# MySensorMicro.net
KiCad netlist of a schematic drawn in EAGLE
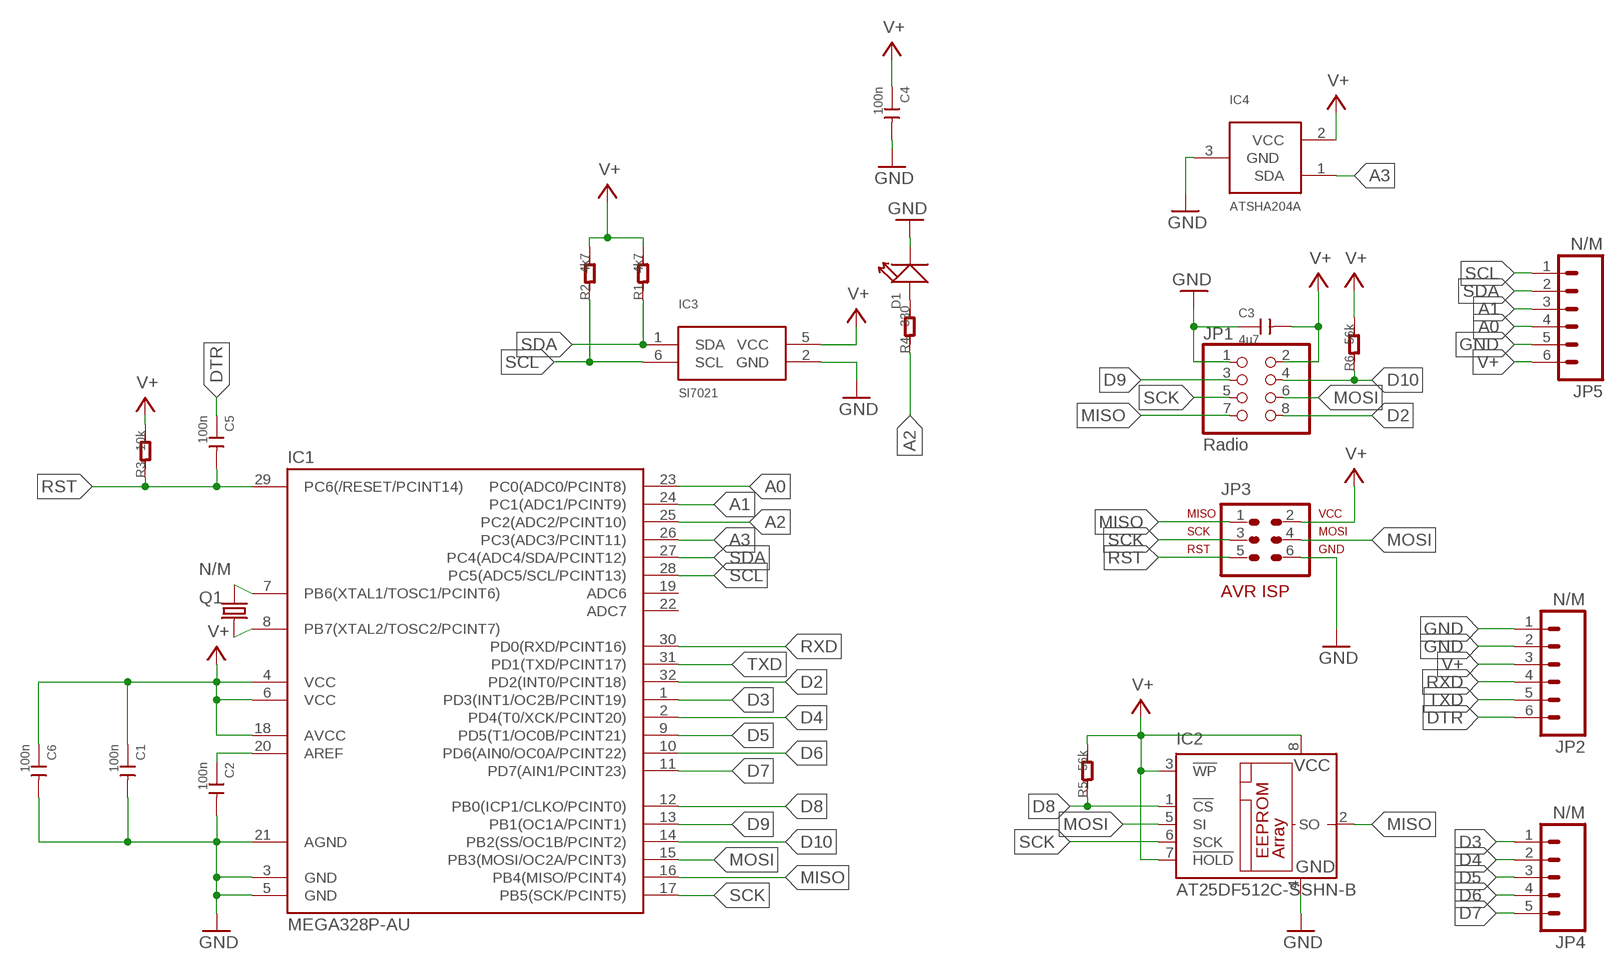
[diagram p0: schematic, sheet 1]

(export (version "E")
  (design (tool "Eeschema 10.0.6"))
  (components
    (comp (ref "C1")
      (value "100n")
      (footprint "eagle-import:C0402")
      (libsource (lib "eagle-import") (part "CAP-0402"))
    )
    (comp (ref "C2")
      (value "100n")
      (footprint "eagle-import:C0402")
      (libsource (lib "eagle-import") (part "CAP-0402"))
    )
    (comp (ref "C3")
      (value "4u7")
      (footprint "eagle-import:C0603")
      (libsource (lib "eagle-import") (part "CAP-0603"))
    )
    (comp (ref "C4")
      (value "100n")
      (footprint "eagle-import:C0402")
      (libsource (lib "eagle-import") (part "CAP-0402"))
    )
    (comp (ref "C5")
      (value "100n")
      (footprint "eagle-import:C0402")
      (libsource (lib "eagle-import") (part "CAP-0402"))
    )
    (comp (ref "C6")
      (value "100n")
      (footprint "eagle-import:C0402")
      (libsource (lib "eagle-import") (part "CAP-0402"))
    )
    (comp (ref "D1")
      (value "LED-0402")
      (footprint "eagle-import:LED-0402")
      (libsource (lib "eagle-import") (part "LED-0402"))
    )
    (comp (ref "IC1")
      (value "MEGA328P-AU")
      (footprint "eagle-import:TQFP32-08")
      (libsource (lib "eagle-import") (part "MEGA48/88/168-AU"))
    )
    (comp (ref "IC2")
      (value "AT25DF512C-SSHN-B")
      (footprint "eagle-import:SO-08")
      (fields (field (name "MF") "MICROCHIP") (field (name "MPN") "25AA080/SN"))
      (libsource (lib "eagle-import") (part "25SNAA080"))
    )
    (comp (ref "IC3")
      (value "SI7021")
      (footprint "eagle-import:DFN6")
      (libsource (lib "eagle-import") (part "SI7021"))
    )
    (comp (ref "IC4")
      (value "ATSHA204A")
      (footprint "eagle-import:SOT23")
      (libsource (lib "eagle-import") (part "ATSHA204A"))
    )
    (comp (ref "JP1")
      (value "Radio")
      (footprint "eagle-import:2X04")
      (libsource (lib "eagle-import") (part "PINHD-2X4"))
    )
    (comp (ref "JP2")
      (value "N/M")
      (footprint "eagle-import:1X06_NO_SILK")
      (libsource (lib "eagle-import") (part "M06NO_SILK_FEMALE_PTH"))
    )
    (comp (ref "JP3")
      (value "N/M")
      (footprint "eagle-import:AVR-ISP-6")
      (libsource (lib "eagle-import") (part "AVR-ISP-6VERT"))
    )
    (comp (ref "JP4")
      (value "N/M")
      (footprint "eagle-import:1X05_NO_SILK")
      (libsource (lib "eagle-import") (part "M05NO_SILK"))
    )
    (comp (ref "JP5")
      (value "N/M")
      (footprint "eagle-import:1X06_NO_SILK")
      (libsource (lib "eagle-import") (part "M06NO_SILK_FEMALE_PTH"))
    )
    (comp (ref "Q1")
      (value "N/M")
      (footprint "eagle-import:2P-L3.2XW1.5MM")
      (libsource (lib "eagle-import") (part "CRYSTAL-306010055"))
    )
    (comp (ref "R1")
      (value "4k7")
      (footprint "eagle-import:R0402")
      (libsource (lib "eagle-import") (part "R-0402"))
    )
    (comp (ref "R2")
      (value "4k7")
      (footprint "eagle-import:R0402")
      (libsource (lib "eagle-import") (part "R-0402"))
    )
    (comp (ref "R3")
      (value "10k")
      (footprint "eagle-import:R0402")
      (libsource (lib "eagle-import") (part "R-0402"))
    )
    (comp (ref "R4")
      (value "330")
      (footprint "eagle-import:R0402")
      (libsource (lib "eagle-import") (part "R-0402"))
    )
    (comp (ref "R5")
      (value "56k")
      (footprint "eagle-import:R0402")
      (libsource (lib "eagle-import") (part "R-0402"))
    )
    (comp (ref "R6")
      (value "56k")
      (footprint "eagle-import:R0402")
      (libsource (lib "eagle-import") (part "R-0402"))
    )
  )
  (nets
    (net (code "1") (name "A0") (class "Default")
      (node (ref "IC1") (pin "23") (pinfunction "PC0(ADC0/PCINT8)_23") (pintype "bidirectional"))
      (node (ref "JP5") (pin "4") (pinfunction "4_4") (pintype "passive"))
    )
    (net (code "2") (name "A1") (class "Default")
      (node (ref "IC1") (pin "24") (pinfunction "PC1(ADC1/PCINT9)_24") (pintype "bidirectional"))
      (node (ref "JP5") (pin "3") (pinfunction "3_3") (pintype "passive"))
    )
    (net (code "3") (name "A2") (class "Default")
      (node (ref "IC1") (pin "25") (pinfunction "PC2(ADC2/PCINT10)_25") (pintype "bidirectional"))
      (node (ref "R4") (pin "1") (pinfunction "1_1") (pintype "bidirectional"))
    )
    (net (code "4") (name "A3") (class "Default")
      (node (ref "IC1") (pin "26") (pinfunction "PC3(ADC3/PCINT11)_26") (pintype "bidirectional"))
      (node (ref "IC4") (pin "1") (pinfunction "SDA_1") (pintype "bidirectional"))
    )
    (net (code "5") (name "D2") (class "Default")
      (node (ref "IC1") (pin "32") (pinfunction "PD2(INT0/PCINT18)_32") (pintype "bidirectional"))
      (node (ref "JP1") (pin "8") (pinfunction "8_8") (pintype "passive"))
    )
    (net (code "6") (name "D3") (class "Default")
      (node (ref "IC1") (pin "1") (pinfunction "PD3(INT1/OC2B/PCINT19)_1") (pintype "bidirectional"))
      (node (ref "JP4") (pin "1") (pinfunction "1_1") (pintype "passive"))
    )
    (net (code "7") (name "D4") (class "Default")
      (node (ref "IC1") (pin "2") (pinfunction "PD4(T0/XCK/PCINT20)_2") (pintype "bidirectional"))
      (node (ref "JP4") (pin "2") (pinfunction "2_2") (pintype "passive"))
    )
    (net (code "8") (name "D5") (class "Default")
      (node (ref "IC1") (pin "9") (pinfunction "PD5(T1/OC0B/PCINT21)_9") (pintype "bidirectional"))
      (node (ref "JP4") (pin "3") (pinfunction "3_3") (pintype "passive"))
    )
    (net (code "9") (name "D6") (class "Default")
      (node (ref "IC1") (pin "10") (pinfunction "PD6(AIN0/OC0A/PCINT22)_10") (pintype "bidirectional"))
      (node (ref "JP4") (pin "4") (pinfunction "4_4") (pintype "passive"))
    )
    (net (code "10") (name "D7") (class "Default")
      (node (ref "IC1") (pin "11") (pinfunction "PD7(AIN1/PCINT23)_11") (pintype "bidirectional"))
      (node (ref "JP4") (pin "5") (pinfunction "5_5") (pintype "passive"))
    )
    (net (code "11") (name "D8") (class "Default")
      (node (ref "IC1") (pin "12") (pinfunction "PB0(ICP1/CLKO/PCINT0)_12") (pintype "bidirectional"))
      (node (ref "IC2") (pin "1") (pinfunction "~{CS}_1") (pintype "input"))
      (node (ref "R5") (pin "1") (pinfunction "1_1") (pintype "bidirectional"))
    )
    (net (code "12") (name "D9") (class "Default")
      (node (ref "IC1") (pin "13") (pinfunction "PB1(OC1A/PCINT1)_13") (pintype "bidirectional"))
      (node (ref "JP1") (pin "3") (pinfunction "3_3") (pintype "passive"))
    )
    (net (code "13") (name "D10") (class "Default")
      (node (ref "IC1") (pin "14") (pinfunction "PB2(SS/OC1B/PCINT2)_14") (pintype "bidirectional"))
      (node (ref "JP1") (pin "4") (pinfunction "4_4") (pintype "passive"))
      (node (ref "R6") (pin "1") (pinfunction "1_1") (pintype "bidirectional"))
    )
    (net (code "14") (name "DTR") (class "Default")
      (node (ref "C5") (pin "1") (pinfunction "1_1") (pintype "passive"))
      (node (ref "JP2") (pin "6") (pinfunction "6_6") (pintype "passive"))
    )
    (net (code "15") (name "GND") (class "Default")
      (node (ref "C1") (pin "2") (pinfunction "2_2") (pintype "passive"))
      (node (ref "C2") (pin "2") (pinfunction "2_2") (pintype "passive"))
      (node (ref "C3") (pin "1") (pinfunction "1_1") (pintype "passive"))
      (node (ref "C4") (pin "2") (pinfunction "2_2") (pintype "passive"))
      (node (ref "C6") (pin "2") (pinfunction "2_2") (pintype "passive"))
      (node (ref "D1") (pin "-") (pinfunction "-_-") (pintype "passive"))
      (node (ref "IC1") (pin "21") (pinfunction "AGND_21") (pintype "power_in"))
      (node (ref "IC1") (pin "3") (pinfunction "GND_3") (pintype "power_in"))
      (node (ref "IC1") (pin "5") (pinfunction "GND_5") (pintype "power_in"))
      (node (ref "IC2") (pin "4") (pinfunction "GND_4") (pintype "power_in"))
      (node (ref "IC3") (pin "2") (pinfunction "GND_2") (pintype "bidirectional"))
      (node (ref "IC4") (pin "3") (pinfunction "GND_3") (pintype "bidirectional"))
      (node (ref "JP1") (pin "1") (pinfunction "1_1") (pintype "passive"))
      (node (ref "JP2") (pin "1") (pinfunction "1_1") (pintype "passive"))
      (node (ref "JP2") (pin "2") (pinfunction "2_2") (pintype "passive"))
      (node (ref "JP3") (pin "6") (pinfunction "6_6") (pintype "passive"))
      (node (ref "JP5") (pin "5") (pinfunction "5_5") (pintype "passive"))
    )
    (net (code "16") (name "MISO") (class "Default")
      (node (ref "IC1") (pin "16") (pinfunction "PB4(MISO/PCINT4)_16") (pintype "bidirectional"))
      (node (ref "IC2") (pin "2") (pinfunction "SO_2") (pintype "bidirectional"))
      (node (ref "JP1") (pin "7") (pinfunction "7_7") (pintype "passive"))
      (node (ref "JP3") (pin "1") (pinfunction "1_1") (pintype "passive"))
    )
    (net (code "17") (name "MOSI") (class "Default")
      (node (ref "IC1") (pin "15") (pinfunction "PB3(MOSI/OC2A/PCINT3)_15") (pintype "bidirectional"))
      (node (ref "IC2") (pin "5") (pinfunction "SI_5") (pintype "input"))
      (node (ref "JP1") (pin "6") (pinfunction "6_6") (pintype "passive"))
      (node (ref "JP3") (pin "4") (pinfunction "4_4") (pintype "passive"))
    )
    (net (code "18") (name "Net-(D1-Pad+)") (class "Default")
      (node (ref "D1") (pin "+") (pinfunction "+_+") (pintype "passive"))
      (node (ref "R4") (pin "2") (pinfunction "2_2") (pintype "bidirectional"))
    )
    (net (code "19") (name "Net-(IC1-AREF)") (class "Default")
      (node (ref "C2") (pin "1") (pinfunction "1_1") (pintype "passive"))
      (node (ref "IC1") (pin "20") (pinfunction "AREF_20") (pintype "passive"))
    )
    (net (code "20") (name "Net-(IC1-PB6(XTAL1{slash}TOSC1{slash}PCINT6))") (class "Default")
      (node (ref "IC1") (pin "7") (pinfunction "PB6(XTAL1/TOSC1/PCINT6)_7") (pintype "bidirectional"))
      (node (ref "Q1") (pin "1") (pinfunction "1_1") (pintype "passive"))
    )
    (net (code "21") (name "Net-(IC1-PB7(XTAL2{slash}TOSC2{slash}PCINT7))") (class "Default")
      (node (ref "IC1") (pin "8") (pinfunction "PB7(XTAL2/TOSC2/PCINT7)_8") (pintype "bidirectional"))
      (node (ref "Q1") (pin "2") (pinfunction "2_2") (pintype "passive"))
    )
    (net (code "22") (name "RST") (class "Default")
      (node (ref "C5") (pin "2") (pinfunction "2_2") (pintype "passive"))
      (node (ref "IC1") (pin "29") (pinfunction "PC6(/RESET/PCINT14)_29") (pintype "bidirectional"))
      (node (ref "JP3") (pin "5") (pinfunction "5_5") (pintype "passive"))
      (node (ref "R3") (pin "1") (pinfunction "1_1") (pintype "bidirectional"))
    )
    (net (code "23") (name "RXD") (class "Default")
      (node (ref "IC1") (pin "30") (pinfunction "PD0(RXD/PCINT16)_30") (pintype "bidirectional"))
      (node (ref "JP2") (pin "4") (pinfunction "4_4") (pintype "passive"))
    )
    (net (code "24") (name "SCK") (class "Default")
      (node (ref "IC1") (pin "17") (pinfunction "PB5(SCK/PCINT5)_17") (pintype "bidirectional"))
      (node (ref "IC2") (pin "6") (pinfunction "SCK_6") (pintype "input"))
      (node (ref "JP1") (pin "5") (pinfunction "5_5") (pintype "passive"))
      (node (ref "JP3") (pin "3") (pinfunction "3_3") (pintype "passive"))
    )
    (net (code "25") (name "SCL") (class "Default")
      (node (ref "IC1") (pin "28") (pinfunction "PC5(ADC5/SCL/PCINT13)_28") (pintype "bidirectional"))
      (node (ref "IC3") (pin "6") (pinfunction "SCL_6") (pintype "bidirectional"))
      (node (ref "JP5") (pin "1") (pinfunction "1_1") (pintype "passive"))
      (node (ref "R2") (pin "1") (pinfunction "1_1") (pintype "bidirectional"))
    )
    (net (code "26") (name "SDA") (class "Default")
      (node (ref "IC1") (pin "27") (pinfunction "PC4(ADC4/SDA/PCINT12)_27") (pintype "bidirectional"))
      (node (ref "IC3") (pin "1") (pinfunction "SDA_1") (pintype "bidirectional"))
      (node (ref "JP5") (pin "2") (pinfunction "2_2") (pintype "passive"))
      (node (ref "R1") (pin "1") (pinfunction "1_1") (pintype "bidirectional"))
    )
    (net (code "27") (name "TXD") (class "Default")
      (node (ref "IC1") (pin "31") (pinfunction "PD1(TXD/PCINT17)_31") (pintype "bidirectional"))
      (node (ref "JP2") (pin "5") (pinfunction "5_5") (pintype "passive"))
    )
    (net (code "28") (name "V+") (class "Default")
      (node (ref "C1") (pin "1") (pinfunction "1_1") (pintype "passive"))
      (node (ref "C3") (pin "2") (pinfunction "2_2") (pintype "passive"))
      (node (ref "C4") (pin "1") (pinfunction "1_1") (pintype "passive"))
      (node (ref "C6") (pin "1") (pinfunction "1_1") (pintype "passive"))
      (node (ref "IC1") (pin "18") (pinfunction "AVCC_18") (pintype "passive"))
      (node (ref "IC1") (pin "4") (pinfunction "VCC_4") (pintype "power_in"))
      (node (ref "IC1") (pin "6") (pinfunction "VCC_6") (pintype "power_in"))
      (node (ref "IC2") (pin "3") (pinfunction "~{WP}_3") (pintype "input"))
      (node (ref "IC2") (pin "7") (pinfunction "~{HOLD}_7") (pintype "input"))
      (node (ref "IC2") (pin "8") (pinfunction "VCC_8") (pintype "power_in"))
      (node (ref "IC3") (pin "5") (pinfunction "VCC_5") (pintype "bidirectional"))
      (node (ref "IC4") (pin "2") (pinfunction "VCC_2") (pintype "bidirectional"))
      (node (ref "JP1") (pin "2") (pinfunction "2_2") (pintype "passive"))
      (node (ref "JP2") (pin "3") (pinfunction "3_3") (pintype "passive"))
      (node (ref "JP3") (pin "2") (pinfunction "2_2") (pintype "passive"))
      (node (ref "JP5") (pin "6") (pinfunction "6_6") (pintype "passive"))
      (node (ref "R1") (pin "2") (pinfunction "2_2") (pintype "bidirectional"))
      (node (ref "R2") (pin "2") (pinfunction "2_2") (pintype "bidirectional"))
      (node (ref "R3") (pin "2") (pinfunction "2_2") (pintype "bidirectional"))
      (node (ref "R5") (pin "2") (pinfunction "2_2") (pintype "bidirectional"))
      (node (ref "R6") (pin "2") (pinfunction "2_2") (pintype "bidirectional"))
    )
    (net (code "29") (name "unconnected-(IC1-ADC6-Pad19)") (class "Default")
      (node (ref "IC1") (pin "19") (pinfunction "ADC6_19") (pintype "passive"))
    )
    (net (code "30") (name "unconnected-(IC1-ADC7-Pad22)") (class "Default")
      (node (ref "IC1") (pin "22") (pinfunction "ADC7_22") (pintype "passive"))
    )
  )
)
